# SpinASM.net
KiCad netlist of a schematic drawn in Altium Designer
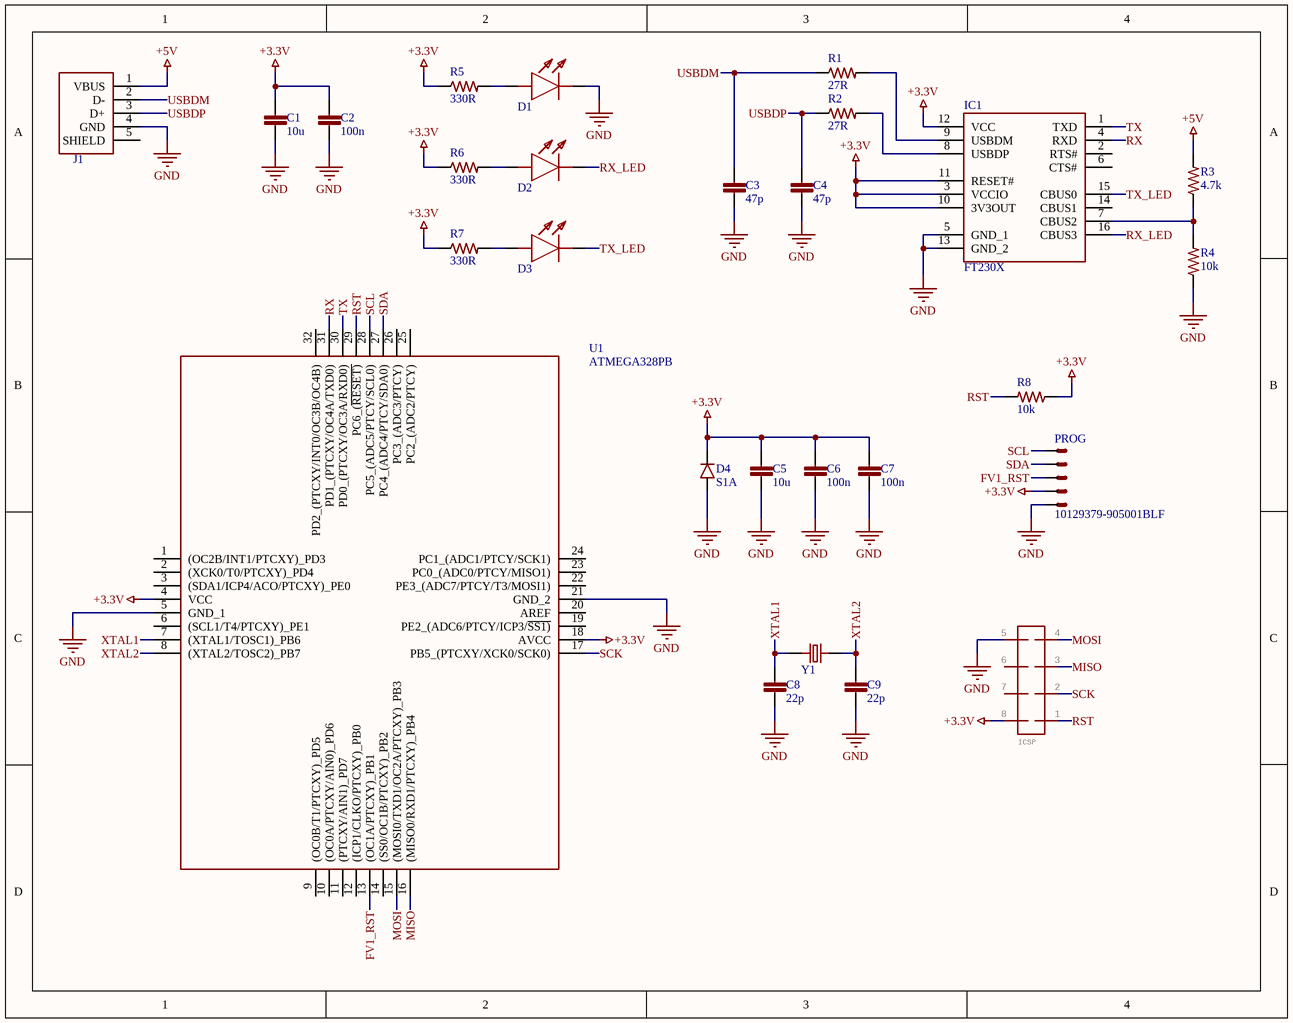
[diagram p0: SpinASM.SchDoc]

(export (version "E")
  (design (tool "Eeschema 10.0.6"))
  (components
    (comp (ref "C1")
      (value "10u")
      (footprint "CHIP_1206")
      (description "CAP CER 10uF 25V X7R 1206")
      (fields
        (field (name "MANUFACTURER") "Taiyo Yuden")
        (field (name "MANUFACTURER PART NUMBER") "TMK316B7106KL-TD")
      )
      (libsource (lib "Pedals SMD") (part "TMK316B7106KL-TD"))
    )
    (comp (ref "C2")
      (value "100n")
      (footprint "CHIP_0603")
      (description "CAP CER 100NF 50V X7R 0603")
      (fields
        (field (name "MANUFACTURER") "Multicomp")
        (field (name "MANUFACTURER PART NUMBER") "MC0603B104K500CT")
      )
      (libsource (lib "Pedals SMD") (part "MC0603B104K500CT"))
    )
    (comp (ref "C3")
      (value "47p")
      (footprint "CHIP_0603")
      (description "CAP CER 47PF 50V C0G/NP0 0603")
      (fields
        (field (name "MANUFACTURER") "Multicomp")
        (field (name "MANUFACTURER PART NUMBER") "MC0603N470J500CT")
      )
      (libsource (lib "Pedals SMD") (part "MC0603N470J500CT"))
    )
    (comp (ref "C4")
      (value "47p")
      (footprint "CHIP_0603")
      (description "CAP CER 47PF 50V C0G/NP0 0603")
      (fields
        (field (name "MANUFACTURER") "Multicomp")
        (field (name "MANUFACTURER PART NUMBER") "MC0603N470J500CT")
      )
      (libsource (lib "Pedals SMD") (part "MC0603N470J500CT"))
    )
    (comp (ref "C5")
      (value "10u")
      (footprint "CHIP_1206")
      (description "CAP CER 10uF 25V X7R 1206")
      (fields
        (field (name "MANUFACTURER") "Taiyo Yuden")
        (field (name "MANUFACTURER PART NUMBER") "TMK316B7106KL-TD")
      )
      (libsource (lib "Pedals SMD") (part "TMK316B7106KL-TD"))
    )
    (comp (ref "C6")
      (value "100n")
      (footprint "CHIP_0603")
      (description "CAP CER 100NF 50V X7R 0603")
      (fields
        (field (name "MANUFACTURER") "Multicomp")
        (field (name "MANUFACTURER PART NUMBER") "MC0603B104K500CT")
      )
      (libsource (lib "Pedals SMD") (part "MC0603B104K500CT"))
    )
    (comp (ref "C7")
      (value "100n")
      (footprint "CHIP_0603")
      (description "CAP CER 100NF 50V X7R 0603")
      (fields
        (field (name "MANUFACTURER") "Multicomp")
        (field (name "MANUFACTURER PART NUMBER") "MC0603B104K500CT")
      )
      (libsource (lib "Pedals SMD") (part "MC0603B104K500CT"))
    )
    (comp (ref "C8")
      (value "22p")
      (footprint "CHIP_0603")
      (description "CAP CER 22PF 50V C0G/NP0 0603")
      (fields
        (field (name "MANUFACTURER") "Multicomp")
        (field (name "MANUFACTURER PART NUMBER") "MC0603N220J500CT")
      )
      (libsource (lib "Pedals SMD") (part "MC0603N220J500CT"))
    )
    (comp (ref "C9")
      (value "22p")
      (footprint "CHIP_0603")
      (description "CAP CER 22PF 50V C0G/NP0 0603")
      (fields
        (field (name "MANUFACTURER") "Multicomp")
        (field (name "MANUFACTURER PART NUMBER") "MC0603N220J500CT")
      )
      (libsource (lib "Pedals SMD") (part "MC0603N220J500CT"))
    )
    (comp (ref "D1")
      (value "GREEN")
      (footprint "LED_0603")
      (description "LED GREEN CLEAR CHIP SMD")
      (fields
        (field (name "MANUFACTURER") "Kingbright")
        (field (name "MANUFACTURER PART NUMBER") "APT1608SGC")
      )
      (libsource (lib "Pedals SMD") (part "APT1608SGC"))
    )
    (comp (ref "D2")
      (value "RED")
      (footprint "LED_0603")
      (description "LED RED CLEAR CHIP SMD")
      (fields
        (field (name "MANUFACTURER") "Kingbright")
        (field (name "MANUFACTURER PART NUMBER") "APT1608EC")
      )
      (libsource (lib "Pedals SMD") (part "APT1608EC"))
    )
    (comp (ref "D3")
      (value "RED")
      (footprint "LED_0603")
      (description "LED RED CLEAR CHIP SMD")
      (fields
        (field (name "MANUFACTURER") "Kingbright")
        (field (name "MANUFACTURER PART NUMBER") "APT1608EC")
      )
      (libsource (lib "Pedals SMD") (part "APT1608EC"))
    )
    (comp (ref "D4")
      (value "S1A")
      (footprint "DO214")
      (description "DIODE GEN PURP 50V 1A SMA")
      (fields (field (name "MANUFACTURER") "ON Semiconductor / Fairchild"))
      (libsource (lib "Pedals SMD") (part "S1A"))
    )
    (comp (ref "IC1")
      (value "FT230X")
      (footprint "TSSOP-16")
      (description "USB-to-UART 1-CH 512byte FIFO 5V 16-Pin SSOP T/R")
      (fields (field (name "MANUFACTURER") "FTDI") (field (name "MANUFACTURER PART NUMBER") "FT230XS-R"))
      (libsource (lib "Pedals SMD") (part "FT230XS-R"))
    )
    (comp (ref "ICSP")
      (value "J_SOICBITE")
      (footprint "SOICBITE")
      (fields (field (name "LIBRARYNAME") "SOICbite_Eagle"))
      (libsource (lib "Pedals") (part "J_SOICBITE"))
    )
    (comp (ref "J1")
      (value "USB_MALE")
      (footprint "USB_MALE")
      (description "Conn USB Type A PL 4 POS 2mm Solder ST SMD 4 Terminal 1 Port")
      (fields
        (field (name "MANUFACTURER") "Kycon")
        (field (name "MANUFACTURER PART NUMBER") "KUSBX-SMT2AP5S-W")
      )
      (libsource (lib "Pedals SMD") (part "KUSBX-SMT2AP5S-W"))
    )
    (comp (ref "PROG")
      (value "10129379-905001BLF")
      (footprint "HEADER_5PINS_MALE_90")
      (description "Conn Unshrouded Header HDR 5 POS 2.54mm Solder RA Thru-Hole Poly Bag")
      (fields (field (name "MANUFACTURER") "ICC"))
      (libsource (lib "Pedals") (part "10129379-905001BLF"))
    )
    (comp (ref "R1")
      (value "27R")
      (footprint "CHIP_R_0603")
      (description "RES SMD 27 OHM 1% 1/10W 0603")
      (fields
        (field (name "MANUFACTURER") "Vishay")
        (field (name "MANUFACTURER PART NUMBER") "CRCW060327R0FKEA")
      )
      (libsource (lib "Pedals SMD") (part "CRCW060327R0FKEA"))
    )
    (comp (ref "R2")
      (value "27R")
      (footprint "CHIP_R_0603")
      (description "RES SMD 27 OHM 1% 1/10W 0603")
      (fields
        (field (name "MANUFACTURER") "Vishay")
        (field (name "MANUFACTURER PART NUMBER") "CRCW060327R0FKEA")
      )
      (libsource (lib "Pedals SMD") (part "CRCW060327R0FKEA"))
    )
    (comp (ref "R3")
      (value "4.7k")
      (footprint "CHIP_R_0603")
      (description "RES SMD 4.7K OHM 1% 1/10W 0603")
      (fields
        (field (name "MANUFACTURER") "Vishay")
        (field (name "MANUFACTURER PART NUMBER") "CRCW06034K70FKEA")
      )
      (libsource (lib "Pedals SMD") (part "CRCW06034K70FKEA"))
    )
    (comp (ref "R4")
      (value "10k")
      (footprint "CHIP_R_0603")
      (description "RES SMD 10K OHM 1% 1/10W 0603")
      (fields
        (field (name "MANUFACTURER") "Vishay")
        (field (name "MANUFACTURER PART NUMBER") "CRCW060310K0FKEA")
      )
      (libsource (lib "Pedals SMD") (part "CRCW060310K0FKEA"))
    )
    (comp (ref "R5")
      (value "330R")
      (footprint "CHIP_R_0603")
      (description "RES SMD 330R OHM 1% 1/10W 0603")
      (fields
        (field (name "MANUFACTURER") "Vishay")
        (field (name "MANUFACTURER PART NUMBER") "CRCW0603330RFKEA")
      )
      (libsource (lib "Pedals SMD") (part "CRCW0603330RFKEA"))
    )
    (comp (ref "R6")
      (value "330R")
      (footprint "CHIP_R_0603")
      (description "RES SMD 330R OHM 1% 1/10W 0603")
      (fields
        (field (name "MANUFACTURER") "Vishay")
        (field (name "MANUFACTURER PART NUMBER") "CRCW0603330RFKEA")
      )
      (libsource (lib "Pedals SMD") (part "CRCW0603330RFKEA"))
    )
    (comp (ref "R7")
      (value "330R")
      (footprint "CHIP_R_0603")
      (description "RES SMD 330R OHM 1% 1/10W 0603")
      (fields
        (field (name "MANUFACTURER") "Vishay")
        (field (name "MANUFACTURER PART NUMBER") "CRCW0603330RFKEA")
      )
      (libsource (lib "Pedals SMD") (part "CRCW0603330RFKEA"))
    )
    (comp (ref "R8")
      (value "10k")
      (footprint "CHIP_R_0603")
      (description "RES SMD 10K OHM 1% 1/10W 0603")
      (fields
        (field (name "MANUFACTURER") "Vishay")
        (field (name "MANUFACTURER PART NUMBER") "CRCW060310K0FKEA")
      )
      (libsource (lib "Pedals SMD") (part "CRCW060310K0FKEA"))
    )
    (comp (ref "U1")
      (value "ATMEGA328PB")
      (footprint "TQFP32")
      (description "IC MCU 8BIT 32KB FLASH 32TQFP")
      (fields
        (field (name "MANUFACTURER") "Microchip")
        (field (name "MANUFACTURER PART NUMBER") "ATMEGA328PB-AU")
      )
      (libsource (lib "Pedals SMD") (part "ATMEGA328PB-AU"))
    )
    (comp (ref "Y1")
      (value "ABM10")
      (footprint "ABM10-167")
      (description "CRYSTAL 12 MHz SMD 28 pF 10 ppm")
      (fields
        (field (name "MANUFACTURER") "Abracon")
        (field (name "MANUFACTURER PART NUMBER") "ABM10-166-12.000MHZ-T3")
      )
      (libsource (lib "Pedals SMD") (part "ABM10-166-12.000MHZ-T3"))
    )
  )
  (nets
    (net (code "1") (name "+3.3V") (class "Default")
      (node (ref "C1") (pin "2") (pinfunction "2_2") (pintype "passive"))
      (node (ref "C2") (pin "1") (pinfunction "1_1") (pintype "passive"))
      (node (ref "C5") (pin "2") (pinfunction "2_2") (pintype "passive"))
      (node (ref "C6") (pin "1") (pinfunction "1_1") (pintype "passive"))
      (node (ref "C7") (pin "1") (pinfunction "1_1") (pintype "passive"))
      (node (ref "D4") (pin "1") (pinfunction "1_1") (pintype "passive"))
      (node (ref "IC1") (pin "10") (pinfunction "3V3OUT_10") (pintype "power_in"))
      (node (ref "IC1") (pin "11") (pinfunction "RESET#_11") (pintype "passive"))
      (node (ref "IC1") (pin "12") (pinfunction "VCC_12") (pintype "power_in"))
      (node (ref "IC1") (pin "3") (pinfunction "VCCIO_3") (pintype "power_in"))
      (node (ref "ICSP") (pin "8") (pinfunction "P$8_8") (pintype "passive"))
      (node (ref "PROG") (pin "2") (pinfunction "S_2") (pintype "passive"))
      (node (ref "R5") (pin "1") (pinfunction "1_1") (pintype "passive"))
      (node (ref "R6") (pin "1") (pinfunction "1_1") (pintype "passive"))
      (node (ref "R7") (pin "1") (pinfunction "1_1") (pintype "passive"))
      (node (ref "R8") (pin "1") (pinfunction "1_1") (pintype "passive"))
      (node (ref "U1") (pin "18") (pinfunction "AVCC_18") (pintype "passive"))
      (node (ref "U1") (pin "4") (pinfunction "VCC_4") (pintype "passive"))
    )
    (net (code "2") (name "+5V") (class "Default")
      (node (ref "J1") (pin "1") (pinfunction "VBUS_1") (pintype "passive"))
      (node (ref "R3") (pin "2") (pinfunction "2_2") (pintype "passive"))
    )
    (net (code "3") (name "/FV1_RST") (class "Default")
      (node (ref "PROG") (pin "3") (pinfunction "S_3") (pintype "passive"))
      (node (ref "U1") (pin "13") (pinfunction "(OC1A/PTCXY)_PB1_13") (pintype "passive"))
    )
    (net (code "4") (name "/MISO") (class "Default")
      (node (ref "ICSP") (pin "3") (pinfunction "P$3_3") (pintype "passive"))
      (node (ref "U1") (pin "16") (pinfunction "(MISO0/RXD1/PTCXY)_PB4_16") (pintype "passive"))
    )
    (net (code "5") (name "/MOSI") (class "Default")
      (node (ref "ICSP") (pin "4") (pinfunction "P$4_4") (pintype "passive"))
      (node (ref "U1") (pin "15") (pinfunction "(MOSI0/TXD1/OC2A/PTCXY)_PB3_15") (pintype "passive"))
    )
    (net (code "6") (name "/RST") (class "Default")
      (node (ref "ICSP") (pin "1") (pinfunction "P$1_1") (pintype "passive"))
      (node (ref "R8") (pin "2") (pinfunction "2_2") (pintype "passive"))
      (node (ref "U1") (pin "29") (pinfunction "PC6_(~{RESET)}_29") (pintype "passive"))
    )
    (net (code "7") (name "/RX") (class "Default")
      (node (ref "IC1") (pin "4") (pinfunction "RXD_4") (pintype "passive"))
      (node (ref "U1") (pin "31") (pinfunction "PD1_(PTCXY/OC4A/TXD0)_31") (pintype "passive"))
    )
    (net (code "8") (name "/RX_LED") (class "Default")
      (node (ref "D2") (pin "1") (pinfunction "K_1") (pintype "passive"))
      (node (ref "IC1") (pin "16") (pinfunction "CBUS3_16") (pintype "passive"))
    )
    (net (code "9") (name "/SCK") (class "Default")
      (node (ref "ICSP") (pin "2") (pinfunction "P$2_2") (pintype "passive"))
      (node (ref "U1") (pin "17") (pinfunction "PB5_(PTCXY/XCK0/SCK0)_17") (pintype "passive"))
    )
    (net (code "10") (name "/SCL") (class "Default")
      (node (ref "PROG") (pin "5") (pinfunction "S_5") (pintype "passive"))
      (node (ref "U1") (pin "28") (pinfunction "PC5_(ADC5/PTCY/SCL0)_28") (pintype "passive"))
    )
    (net (code "11") (name "/SDA") (class "Default")
      (node (ref "PROG") (pin "4") (pinfunction "S_4") (pintype "passive"))
      (node (ref "U1") (pin "27") (pinfunction "PC4_(ADC4/PTCY/SDA0)_27") (pintype "passive"))
    )
    (net (code "12") (name "/TX") (class "Default")
      (node (ref "IC1") (pin "1") (pinfunction "TXD_1") (pintype "passive"))
      (node (ref "U1") (pin "30") (pinfunction "PD0_(PTCXY/OC3A/RXD0)_30") (pintype "passive"))
    )
    (net (code "13") (name "/TX_LED") (class "Default")
      (node (ref "D3") (pin "1") (pinfunction "K_1") (pintype "passive"))
      (node (ref "IC1") (pin "15") (pinfunction "CBUS0_15") (pintype "passive"))
    )
    (net (code "14") (name "/USBDM") (class "Default")
      (node (ref "C3") (pin "1") (pinfunction "1_1") (pintype "passive"))
      (node (ref "J1") (pin "2") (pinfunction "D-_2") (pintype "passive"))
      (node (ref "R1") (pin "1") (pinfunction "1_1") (pintype "passive"))
    )
    (net (code "15") (name "/USBDP") (class "Default")
      (node (ref "C4") (pin "1") (pinfunction "1_1") (pintype "passive"))
      (node (ref "J1") (pin "3") (pinfunction "D+_3") (pintype "passive"))
      (node (ref "R2") (pin "1") (pinfunction "1_1") (pintype "passive"))
    )
    (net (code "16") (name "/XTAL1") (class "Default")
      (node (ref "C8") (pin "1") (pinfunction "1_1") (pintype "passive"))
      (node (ref "U1") (pin "7") (pinfunction "(XTAL1/TOSC1)_PB6_7") (pintype "passive"))
      (node (ref "Y1") (pin "1") (pinfunction "1_1") (pintype "passive"))
    )
    (net (code "17") (name "/XTAL2") (class "Default")
      (node (ref "C9") (pin "1") (pinfunction "1_1") (pintype "passive"))
      (node (ref "U1") (pin "8") (pinfunction "(XTAL2/TOSC2)_PB7_8") (pintype "passive"))
      (node (ref "Y1") (pin "2") (pinfunction "2_2") (pintype "passive"))
    )
    (net (code "18") (name "GND") (class "Default")
      (node (ref "C1") (pin "1") (pinfunction "1_1") (pintype "passive"))
      (node (ref "C2") (pin "2") (pinfunction "2_2") (pintype "passive"))
      (node (ref "C3") (pin "2") (pinfunction "2_2") (pintype "passive"))
      (node (ref "C4") (pin "2") (pinfunction "2_2") (pintype "passive"))
      (node (ref "C5") (pin "1") (pinfunction "1_1") (pintype "passive"))
      (node (ref "C6") (pin "2") (pinfunction "2_2") (pintype "passive"))
      (node (ref "C7") (pin "2") (pinfunction "2_2") (pintype "passive"))
      (node (ref "C8") (pin "2") (pinfunction "2_2") (pintype "passive"))
      (node (ref "C9") (pin "2") (pinfunction "2_2") (pintype "passive"))
      (node (ref "D1") (pin "1") (pinfunction "K_1") (pintype "passive"))
      (node (ref "D4") (pin "2") (pinfunction "2_2") (pintype "passive"))
      (node (ref "IC1") (pin "13") (pinfunction "GND_2_13") (pintype "power_in"))
      (node (ref "IC1") (pin "5") (pinfunction "GND_1_5") (pintype "power_in"))
      (node (ref "ICSP") (pin "5") (pinfunction "P$5_5") (pintype "passive"))
      (node (ref "J1") (pin "4") (pinfunction "GND_4") (pintype "passive"))
      (node (ref "PROG") (pin "1") (pinfunction "S_1") (pintype "passive"))
      (node (ref "R4") (pin "1") (pinfunction "1_1") (pintype "passive"))
      (node (ref "U1") (pin "21") (pinfunction "GND_2_21") (pintype "passive"))
      (node (ref "U1") (pin "5") (pinfunction "GND_1_5") (pintype "passive"))
    )
    (net (code "19") (name "Net-(D1-A)") (class "Default")
      (node (ref "D1") (pin "2") (pinfunction "A_2") (pintype "passive"))
      (node (ref "R5") (pin "2") (pinfunction "2_2") (pintype "passive"))
    )
    (net (code "20") (name "Net-(D2-A)") (class "Default")
      (node (ref "D2") (pin "2") (pinfunction "A_2") (pintype "passive"))
      (node (ref "R6") (pin "2") (pinfunction "2_2") (pintype "passive"))
    )
    (net (code "21") (name "Net-(D3-A)") (class "Default")
      (node (ref "D3") (pin "2") (pinfunction "A_2") (pintype "passive"))
      (node (ref "R7") (pin "2") (pinfunction "2_2") (pintype "passive"))
    )
    (net (code "22") (name "Net-(IC1-CBUS2)") (class "Default")
      (node (ref "IC1") (pin "7") (pinfunction "CBUS2_7") (pintype "passive"))
      (node (ref "R3") (pin "1") (pinfunction "1_1") (pintype "passive"))
      (node (ref "R4") (pin "2") (pinfunction "2_2") (pintype "passive"))
    )
    (net (code "23") (name "Net-(IC1-USBDM)") (class "Default")
      (node (ref "IC1") (pin "9") (pinfunction "USBDM_9") (pintype "passive"))
      (node (ref "R1") (pin "2") (pinfunction "2_2") (pintype "passive"))
    )
    (net (code "24") (name "Net-(IC1-USBDP)") (class "Default")
      (node (ref "IC1") (pin "8") (pinfunction "USBDP_8") (pintype "passive"))
      (node (ref "R2") (pin "2") (pinfunction "2_2") (pintype "passive"))
    )
    (net (code "25") (name "unconnected-(IC1-CBUS1-Pad14)") (class "Default")
      (node (ref "IC1") (pin "14") (pinfunction "CBUS1_14") (pintype "passive"))
    )
    (net (code "26") (name "unconnected-(IC1-CTS#-Pad6)") (class "Default")
      (node (ref "IC1") (pin "6") (pinfunction "CTS#_6") (pintype "passive"))
    )
    (net (code "27") (name "unconnected-(IC1-RTS#-Pad2)") (class "Default")
      (node (ref "IC1") (pin "2") (pinfunction "RTS#_2") (pintype "passive"))
    )
    (net (code "28") (name "unconnected-(ICSP-P$6-Pad6)") (class "Default")
      (node (ref "ICSP") (pin "6") (pinfunction "P$6_6") (pintype "passive"))
    )
    (net (code "29") (name "unconnected-(ICSP-P$7-Pad7)") (class "Default")
      (node (ref "ICSP") (pin "7") (pinfunction "P$7_7") (pintype "passive"))
    )
    (net (code "30") (name "unconnected-(J1-SHIELD-Pad5)") (class "Default")
      (node (ref "J1") (pin "5") (pinfunction "SHIELD_5") (pintype "passive"))
    )
    (net (code "31") (name "unconnected-(U1-(ICP1{slash}CLKO{slash}PTCXY)_PB0-Pad12)") (class "Default")
      (node (ref "U1") (pin "12") (pinfunction "(ICP1/CLKO/PTCXY)_PB0_12") (pintype "passive"))
    )
    (net (code "32") (name "unconnected-(U1-(OC0A{slash}PTCXY{slash}AIN0)_PD6-Pad10)") (class "Default")
      (node (ref "U1") (pin "10") (pinfunction "(OC0A/PTCXY/AIN0)_PD6_10") (pintype "passive"))
    )
    (net (code "33") (name "unconnected-(U1-(OC0B{slash}T1{slash}PTCXY)_PD5-Pad9)") (class "Default")
      (node (ref "U1") (pin "9") (pinfunction "(OC0B/T1/PTCXY)_PD5_9") (pintype "passive"))
    )
    (net (code "34") (name "unconnected-(U1-(OC2B{slash}INT1{slash}PTCXY)_PD3-Pad1)") (class "Default")
      (node (ref "U1") (pin "1") (pinfunction "(OC2B/INT1/PTCXY)_PD3_1") (pintype "passive"))
    )
    (net (code "35") (name "unconnected-(U1-(PTCXY{slash}AIN1)_PD7-Pad11)") (class "Default")
      (node (ref "U1") (pin "11") (pinfunction "(PTCXY/AIN1)_PD7_11") (pintype "passive"))
    )
    (net (code "36") (name "unconnected-(U1-(SCL1{slash}T4{slash}PTCXY)_PE1-Pad6)") (class "Default")
      (node (ref "U1") (pin "6") (pinfunction "(SCL1/T4/PTCXY)_PE1_6") (pintype "passive"))
    )
    (net (code "37") (name "unconnected-(U1-(SDA1{slash}ICP4{slash}ACO{slash}PTCXY)_PE0-Pad3)") (class "Default")
      (node (ref "U1") (pin "3") (pinfunction "(SDA1/ICP4/ACO/PTCXY)_PE0_3") (pintype "passive"))
    )
    (net (code "38") (name "unconnected-(U1-(SS0{slash}OC1B{slash}PTCXY)_PB2-Pad14)") (class "Default")
      (node (ref "U1") (pin "14") (pinfunction "(SS0/OC1B/PTCXY)_PB2_14") (pintype "passive"))
    )
    (net (code "39") (name "unconnected-(U1-(XCK0{slash}T0{slash}PTCXY)_PD4-Pad2)") (class "Default")
      (node (ref "U1") (pin "2") (pinfunction "(XCK0/T0/PTCXY)_PD4_2") (pintype "passive"))
    )
    (net (code "40") (name "unconnected-(U1-AREF-Pad20)") (class "Default")
      (node (ref "U1") (pin "20") (pinfunction "AREF_20") (pintype "passive"))
    )
    (net (code "41") (name "unconnected-(U1-PC0_(ADC0{slash}PTCY{slash}MISO1)-Pad23)") (class "Default")
      (node (ref "U1") (pin "23") (pinfunction "PC0_(ADC0/PTCY/MISO1)_23") (pintype "passive"))
    )
    (net (code "42") (name "unconnected-(U1-PC1_(ADC1{slash}PTCY{slash}SCK1)-Pad24)") (class "Default")
      (node (ref "U1") (pin "24") (pinfunction "PC1_(ADC1/PTCY/SCK1)_24") (pintype "passive"))
    )
    (net (code "43") (name "unconnected-(U1-PC2_(ADC2{slash}PTCY)-Pad25)") (class "Default")
      (node (ref "U1") (pin "25") (pinfunction "PC2_(ADC2/PTCY)_25") (pintype "passive"))
    )
    (net (code "44") (name "unconnected-(U1-PC3_(ADC3{slash}PTCY)-Pad26)") (class "Default")
      (node (ref "U1") (pin "26") (pinfunction "PC3_(ADC3/PTCY)_26") (pintype "passive"))
    )
    (net (code "45") (name "unconnected-(U1-PD2_(PTCXY{slash}INT0{slash}OC3B{slash}OC4B)-Pad32)") (class "Default")
      (node (ref "U1") (pin "32") (pinfunction "PD2_(PTCXY/INT0/OC3B/OC4B)_32") (pintype "passive"))
    )
    (net (code "46") (name "unconnected-(U1-PE2_(ADC6{slash}PTCY{slash}ICP3{slash}~{SS1)}-Pad19)") (class "Default")
      (node (ref "U1") (pin "19") (pinfunction "PE2_(ADC6/PTCY/ICP3/~{SS1)}_19") (pintype "passive"))
    )
    (net (code "47") (name "unconnected-(U1-PE3_(ADC7{slash}PTCY{slash}T3{slash}MOSI1)-Pad22)") (class "Default")
      (node (ref "U1") (pin "22") (pinfunction "PE3_(ADC7/PTCY/T3/MOSI1)_22") (pintype "passive"))
    )
  )
)
